# Power.net
KiCad netlist of a schematic drawn in Altium Designer
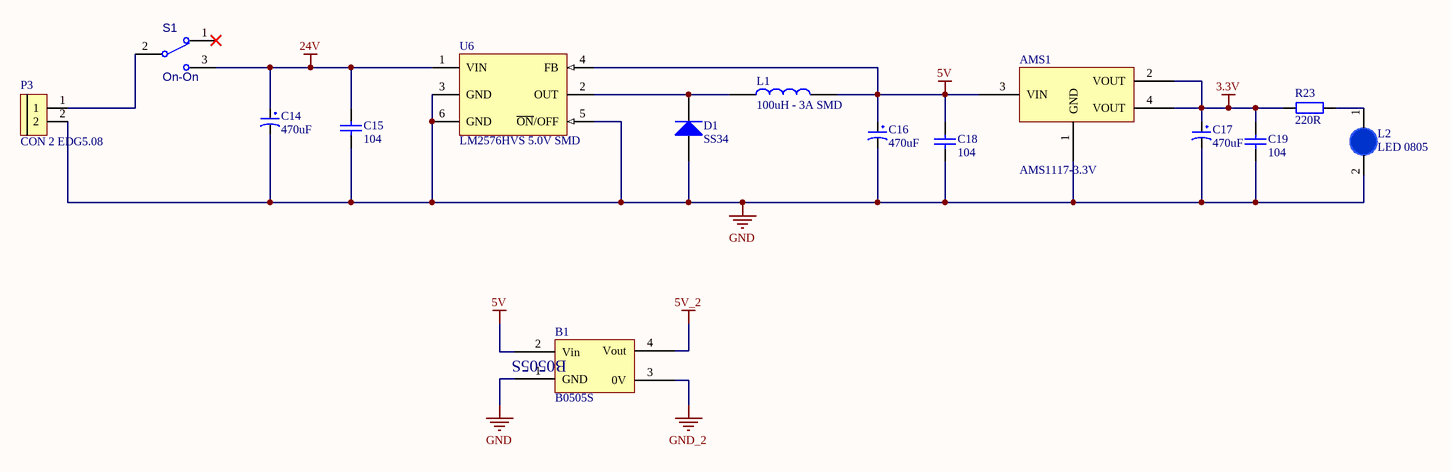
[diagram p0: Power.SchDoc]

(export (version "E")
  (design (tool "Eeschema 10.0.6"))
  (components
    (comp (ref "AMS1")
      (value "AMS1117-3.3V")
      (footprint "SOT223")
      (description "Dán")
      (libsource (lib "Altium_Lib_by_KhueNguyenCreator") (part "AMS1117 SMD"))
    )
    (comp (ref "B1")
      (value "B0505S")
      (footprint "B0505S")
      (description "Cắm")
      (libsource (lib "Altium_Lib_by_KhueNguyenCreator") (part "B0505S"))
    )
    (comp (ref "C14")
      (value "470uF")
      (footprint "tu hoa 10mm")
      (description "Cắm")
      (libsource (lib "Altium_Lib_by_KhueNguyenCreator") (part "Tu Hoa 470uF 35V 10x15"))
    )
    (comp (ref "C15")
      (value "104")
      (footprint "tu 0603")
      (description "Dán")
      (libsource (lib "Altium_Lib_by_KhueNguyenCreator") (part "Tu 0603 104 50V 10%"))
    )
    (comp (ref "C16")
      (value "470uF")
      (footprint "tu hoa 10mm")
      (description "Cắm")
      (libsource (lib "Altium_Lib_by_KhueNguyenCreator") (part "Tu Hoa 470uF 35V 10x15"))
    )
    (comp (ref "C17")
      (value "470uF")
      (footprint "tu hoa 10mm")
      (description "Cắm")
      (libsource (lib "Altium_Lib_by_KhueNguyenCreator") (part "Tu Hoa 470uF 35V 10x15"))
    )
    (comp (ref "C18")
      (value "104")
      (footprint "tu 0603")
      (description "Dán")
      (libsource (lib "Altium_Lib_by_KhueNguyenCreator") (part "Tu 0603 104 50V 10%"))
    )
    (comp (ref "C19")
      (value "104")
      (footprint "tu 0603")
      (description "Dán")
      (libsource (lib "Altium_Lib_by_KhueNguyenCreator") (part "Tu 0603 104 50V 10%"))
    )
    (comp (ref "D1")
      (value "SS34")
      (footprint "DIODE SMA")
      (description "Dán")
      (libsource (lib "Altium_Lib_by_KhueNguyenCreator") (part "Diode SS34 ( 1N5822 )"))
    )
    (comp (ref "L1")
      (value "100uH - 3A SMD")
      (footprint "Cuon Cam 12x12x10")
      (description "Dán")
      (libsource (lib "Altium_Lib_by_KhueNguyenCreator") (part "CUON CAM 100uH SMD"))
    )
    (comp (ref "L2")
      (value "LED 0805")
      (footprint "LED-0805-Blue")
      (description "Dán")
      (libsource (lib "Altium_Lib_by_KhueNguyenCreator") (part "LED 0805 Xanh Duong"))
    )
    (comp (ref "P3")
      (value "CON 2 EDG5.08")
      (footprint "CON 2 2EDG5.08")
      (description "Cắm")
      (libsource (lib "Altium_Lib_by_KhueNguyenCreator") (part "CON 2 EDG5.08"))
    )
    (comp (ref "R23")
      (value "220R")
      (footprint "tro smd 0603")
      (description "Dán")
      (libsource (lib "Altium_Lib_by_KhueNguyenCreator") (part "Tro 0603 5% 220R"))
    )
    (comp (ref "S1")
      (value "ON-ON")
      (footprint "SWITCH_SPDT_SLIDER")
      (description "Switch THD vertical toggle SPDT")
      (fields (field (name "SWITCH FUNCTION") "On-On"))
      (libsource (lib "My library altium") (part "SW_THD_SPDT_On-On"))
    )
    (comp (ref "U6")
      (value "LM2576HVS 5.0V SMD")
      (footprint "TO263-5")
      (description "Dán")
      (libsource (lib "Altium_Lib_by_KhueNguyenCreator") (part "LM2576HVS 5.0V SMD"))
    )
  )
  (nets
    (net (code "1") (name "3.3V") (class "Default")
      (node (ref "AMS1") (pin "2") (pinfunction "VOUT_2") (pintype "passive"))
      (node (ref "AMS1") (pin "4") (pinfunction "VOUT_4") (pintype "passive"))
      (node (ref "C17") (pin "1") (pinfunction "1_1") (pintype "passive"))
      (node (ref "C19") (pin "1") (pinfunction "1_1") (pintype "passive"))
      (node (ref "R23") (pin "1") (pinfunction "1_1") (pintype "passive"))
    )
    (net (code "2") (name "5V") (class "Default")
      (node (ref "AMS1") (pin "3") (pinfunction "VIN_3") (pintype "passive"))
      (node (ref "B1") (pin "2") (pinfunction "Vin_2") (pintype "passive"))
      (node (ref "C16") (pin "1") (pinfunction "1_1") (pintype "passive"))
      (node (ref "C18") (pin "1") (pinfunction "1_1") (pintype "passive"))
      (node (ref "L1") (pin "2") (pinfunction "2_2") (pintype "passive"))
      (node (ref "U6") (pin "4") (pinfunction "FB_4") (pintype "input"))
    )
    (net (code "3") (name "5V_2") (class "Default")
      (node (ref "B1") (pin "4") (pinfunction "Vout_4") (pintype "passive"))
    )
    (net (code "4") (name "24V") (class "Default")
      (node (ref "C14") (pin "1") (pinfunction "1_1") (pintype "passive"))
      (node (ref "C15") (pin "1") (pinfunction "1_1") (pintype "passive"))
      (node (ref "S1") (pin "3") (pinfunction "3_3") (pintype "passive"))
      (node (ref "U6") (pin "1") (pinfunction "VIN_1") (pintype "power_in"))
    )
    (net (code "5") (name "GND") (class "Default")
      (node (ref "AMS1") (pin "1") (pinfunction "GND_1") (pintype "passive"))
      (node (ref "B1") (pin "1") (pinfunction "GND_1") (pintype "passive"))
      (node (ref "C14") (pin "2") (pinfunction "2_2") (pintype "passive"))
      (node (ref "C15") (pin "2") (pinfunction "2_2") (pintype "passive"))
      (node (ref "C16") (pin "2") (pinfunction "2_2") (pintype "passive"))
      (node (ref "C17") (pin "2") (pinfunction "2_2") (pintype "passive"))
      (node (ref "C18") (pin "2") (pinfunction "2_2") (pintype "passive"))
      (node (ref "C19") (pin "2") (pinfunction "2_2") (pintype "passive"))
      (node (ref "D1") (pin "1") (pinfunction "A_1") (pintype "passive"))
      (node (ref "L2") (pin "2") (pinfunction "K_2") (pintype "passive"))
      (node (ref "P3") (pin "2") (pinfunction "2_2") (pintype "passive"))
      (node (ref "U6") (pin "3") (pinfunction "GND_3") (pintype "power_in"))
      (node (ref "U6") (pin "5") (pinfunction "~{ON}/OFF_5") (pintype "input"))
      (node (ref "U6") (pin "6") (pinfunction "GND_6") (pintype "passive"))
    )
    (net (code "6") (name "GND_2") (class "Default")
      (node (ref "B1") (pin "3") (pinfunction "0V_3") (pintype "passive"))
    )
    (net (code "7") (name "Net-(D1-K)") (class "Default")
      (node (ref "D1") (pin "2") (pinfunction "K_2") (pintype "passive"))
      (node (ref "L1") (pin "1") (pinfunction "1_1") (pintype "passive"))
      (node (ref "U6") (pin "2") (pinfunction "OUT_2") (pintype "power_in"))
    )
    (net (code "8") (name "Net-(L2-A)") (class "Default")
      (node (ref "L2") (pin "1") (pinfunction "A_1") (pintype "passive"))
      (node (ref "R23") (pin "2") (pinfunction "2_2") (pintype "passive"))
    )
    (net (code "9") (name "Net-(P3-Pad1)") (class "Default")
      (node (ref "P3") (pin "1") (pinfunction "1_1") (pintype "passive"))
      (node (ref "S1") (pin "2") (pinfunction "2_2") (pintype "passive"))
    )
    (net (code "10") (name "unconnected-(S1-Pad1)") (class "Default")
      (node (ref "S1") (pin "1") (pinfunction "1_1") (pintype "passive+no_connect"))
    )
  )
)
